# Isolation.net
KiCad netlist of a schematic drawn in Altium Designer
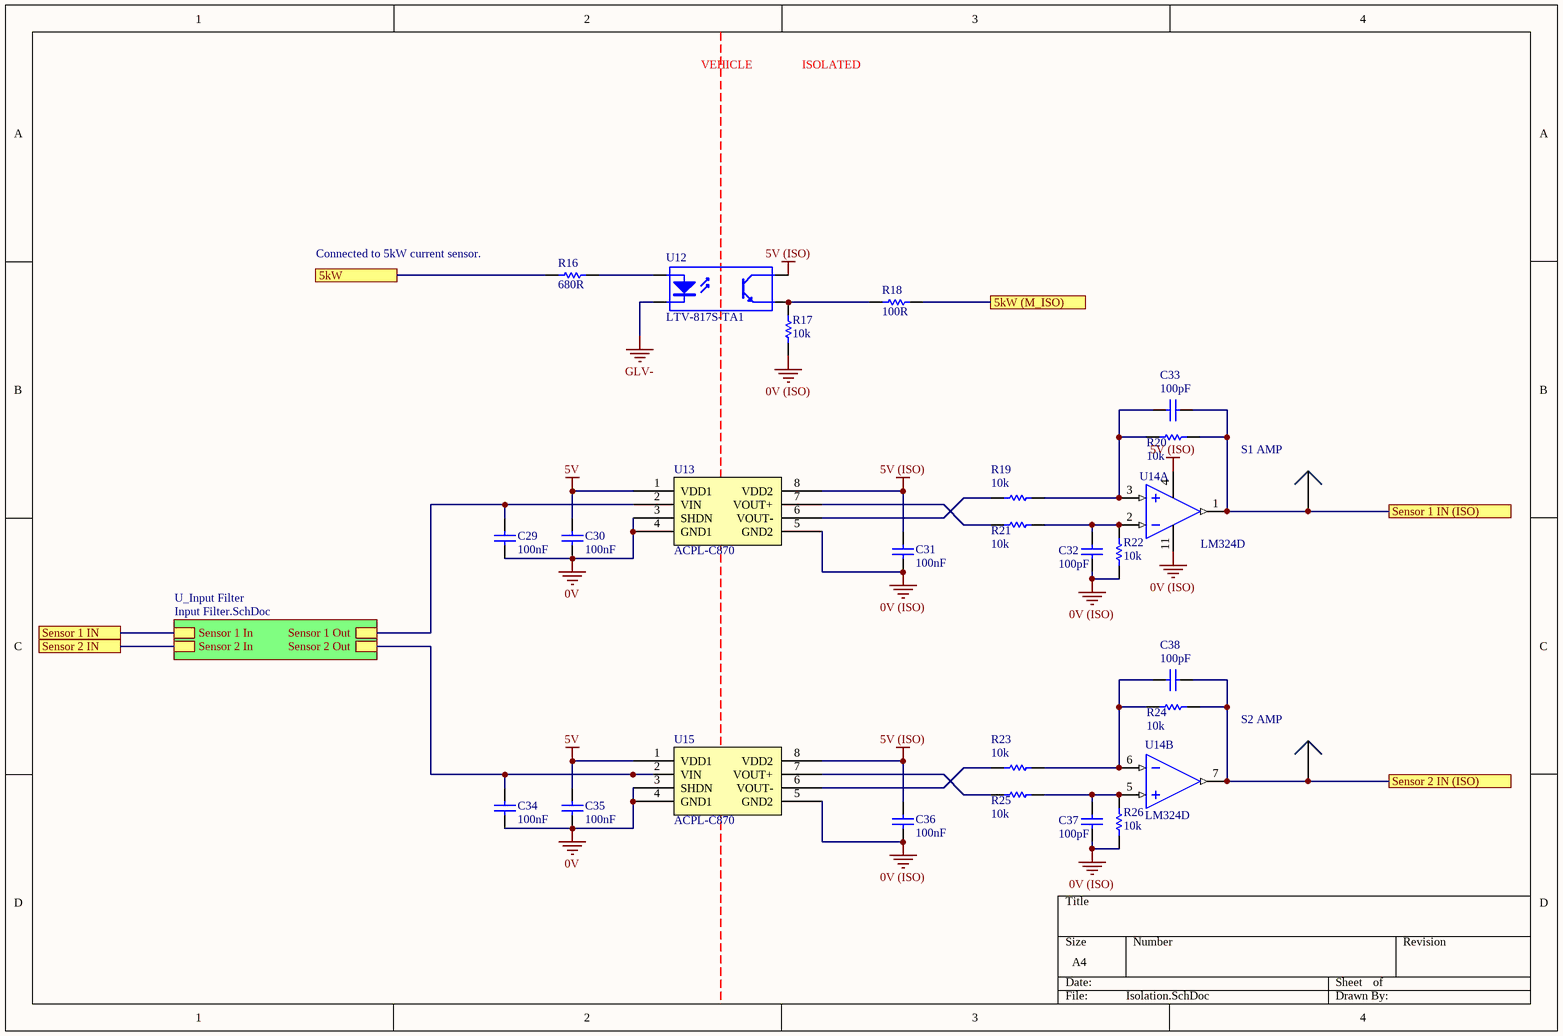
[diagram p0: Isolation.SchDoc]

(export (version "E")
  (design (tool "Eeschema 10.0.6"))
  (components
    (comp (ref "C29")
      (value "100nF")
      (footprint "0805")
      (fields
        (field (name "PART NUMBER") "GCM21BR71H104KA37L")
        (field (name "TOLERANCE") "±10%")
        (field (name "MANUFACTURER") "muRata")
      )
      (libsource (lib "ts_20-standard-library") (part "Capacitor"))
    )
    (comp (ref "C30")
      (value "100nF")
      (footprint "0805")
      (fields
        (field (name "PART NUMBER") "GCM21BR71H104KA37L")
        (field (name "TOLERANCE") "±10%")
        (field (name "MANUFACTURER") "muRata")
      )
      (libsource (lib "ts_20-standard-library") (part "Capacitor"))
    )
    (comp (ref "C31")
      (value "100nF")
      (footprint "0805")
      (fields
        (field (name "PART NUMBER") "GCM21BR71H104KA37L")
        (field (name "TOLERANCE") "±10%")
        (field (name "MANUFACTURER") "muRata")
      )
      (libsource (lib "ts_20-standard-library") (part "Capacitor"))
    )
    (comp (ref "C32")
      (value "100pF")
      (footprint "0805")
      (fields
        (field (name "PART NUMBER") "GCM2165C1H101JA16D")
        (field (name "TOLERANCE") "±5%")
        (field (name "MANUFACTURER") "muRata")
      )
      (libsource (lib "ts_20-standard-library") (part "Capacitor"))
    )
    (comp (ref "C33")
      (value "100pF")
      (footprint "0805")
      (fields
        (field (name "PART NUMBER") "GCM2165C1H101JA16D")
        (field (name "TOLERANCE") "±5%")
        (field (name "MANUFACTURER") "muRata")
      )
      (libsource (lib "ts_20-standard-library") (part "Capacitor"))
    )
    (comp (ref "C34")
      (value "100nF")
      (footprint "0805")
      (fields
        (field (name "PART NUMBER") "GCM21BR71H104KA37L")
        (field (name "TOLERANCE") "±10%")
        (field (name "MANUFACTURER") "muRata")
      )
      (libsource (lib "ts_20-standard-library") (part "Capacitor"))
    )
    (comp (ref "C35")
      (value "100nF")
      (footprint "0805")
      (fields
        (field (name "PART NUMBER") "GCM21BR71H104KA37L")
        (field (name "TOLERANCE") "±10%")
        (field (name "MANUFACTURER") "muRata")
      )
      (libsource (lib "ts_20-standard-library") (part "Capacitor"))
    )
    (comp (ref "C36")
      (value "100nF")
      (footprint "0805")
      (fields
        (field (name "PART NUMBER") "GCM21BR71H104KA37L")
        (field (name "TOLERANCE") "±10%")
        (field (name "MANUFACTURER") "muRata")
      )
      (libsource (lib "ts_20-standard-library") (part "Capacitor"))
    )
    (comp (ref "C37")
      (value "100pF")
      (footprint "0805")
      (fields
        (field (name "PART NUMBER") "GCM2165C1H101JA16D")
        (field (name "TOLERANCE") "±5%")
        (field (name "MANUFACTURER") "muRata")
      )
      (libsource (lib "ts_20-standard-library") (part "Capacitor"))
    )
    (comp (ref "C38")
      (value "100pF")
      (footprint "0805")
      (fields
        (field (name "PART NUMBER") "GCM2165C1H101JA16D")
        (field (name "TOLERANCE") "±5%")
        (field (name "MANUFACTURER") "muRata")
      )
      (libsource (lib "ts_20-standard-library") (part "Capacitor"))
    )
    (comp (ref "R16")
      (value "680R")
      (footprint "0805")
      (fields
        (field (name "PART NUMBER") "RC0805FR07680RL")
        (field (name "MANUFACTURER") "YAGEO")
        (field (name "TOLERANCE") "0.01")
      )
      (libsource (lib "ts_20-standard-library") (part "Resistor"))
    )
    (comp (ref "R17")
      (value "10k")
      (footprint "0805")
      (fields
        (field (name "PART NUMBER") "RC0805FR0710KL")
        (field (name "MANUFACTURER") "YAGEO")
        (field (name "TOLERANCE") "0.01")
      )
      (libsource (lib "ts_20-standard-library") (part "Resistor"))
    )
    (comp (ref "R18")
      (value "100R")
      (footprint "0805")
      (fields
        (field (name "PART NUMBER") "RC0805FR07100RL")
        (field (name "MANUFACTURER") "YAGEO")
        (field (name "TOLERANCE") "0.01")
      )
      (libsource (lib "ts_20-standard-library") (part "Resistor"))
    )
    (comp (ref "R19")
      (value "10k")
      (footprint "0805")
      (fields
        (field (name "PART NUMBER") "RC0805FR0710KL")
        (field (name "MANUFACTURER") "YAGEO")
        (field (name "TOLERANCE") "0.01")
      )
      (libsource (lib "ts_20-standard-library") (part "Resistor"))
    )
    (comp (ref "R20")
      (value "10k")
      (footprint "0805")
      (fields
        (field (name "PART NUMBER") "RC0805FR0710KL")
        (field (name "MANUFACTURER") "YAGEO")
        (field (name "TOLERANCE") "0.01")
      )
      (libsource (lib "ts_20-standard-library") (part "Resistor"))
    )
    (comp (ref "R21")
      (value "10k")
      (footprint "0805")
      (fields
        (field (name "PART NUMBER") "RC0805FR0710KL")
        (field (name "MANUFACTURER") "YAGEO")
        (field (name "TOLERANCE") "0.01")
      )
      (libsource (lib "ts_20-standard-library") (part "Resistor"))
    )
    (comp (ref "R22")
      (value "10k")
      (footprint "0805")
      (fields
        (field (name "PART NUMBER") "RC0805FR0710KL")
        (field (name "MANUFACTURER") "YAGEO")
        (field (name "TOLERANCE") "0.01")
      )
      (libsource (lib "ts_20-standard-library") (part "Resistor"))
    )
    (comp (ref "R23")
      (value "10k")
      (footprint "0805")
      (fields
        (field (name "PART NUMBER") "RC0805FR0710KL")
        (field (name "MANUFACTURER") "YAGEO")
        (field (name "TOLERANCE") "0.01")
      )
      (libsource (lib "ts_20-standard-library") (part "Resistor"))
    )
    (comp (ref "R24")
      (value "10k")
      (footprint "0805")
      (fields
        (field (name "PART NUMBER") "RC0805FR0710KL")
        (field (name "MANUFACTURER") "YAGEO")
        (field (name "TOLERANCE") "0.01")
      )
      (libsource (lib "ts_20-standard-library") (part "Resistor"))
    )
    (comp (ref "R25")
      (value "10k")
      (footprint "0805")
      (fields
        (field (name "PART NUMBER") "RC0805FR0710KL")
        (field (name "MANUFACTURER") "YAGEO")
        (field (name "TOLERANCE") "0.01")
      )
      (libsource (lib "ts_20-standard-library") (part "Resistor"))
    )
    (comp (ref "R26")
      (value "10k")
      (footprint "0805")
      (fields
        (field (name "PART NUMBER") "RC0805FR0710KL")
        (field (name "MANUFACTURER") "YAGEO")
        (field (name "TOLERANCE") "0.01")
      )
      (libsource (lib "ts_20-standard-library") (part "Resistor"))
    )
    (comp (ref "S1 AMP")
      (value "0mm")
      (footprint "SMD Test Point")
      (fields (field (name "PART NUMBER") "SMD Test Point") (field (name "CONTACT") "NA"))
      (libsource (lib "ts_20-standard-connectors") (part "Test Point"))
    )
    (comp (ref "S2 AMP")
      (value "0mm")
      (footprint "SMD Test Point")
      (fields (field (name "PART NUMBER") "SMD Test Point") (field (name "CONTACT") "NA"))
      (libsource (lib "ts_20-standard-connectors") (part "Test Point"))
    )
    (comp (ref "U12")
      (value "LTV-817S-TA1")
      (footprint "ON 4-SMD")
      (description "35V 50ma Optocoupler (VF=1.2V)")
      (fields
        (field (name "MANUFACTURER") "Lite-On Inc")
        (field (name "DIGIKEY PART NUMBER") "160-1893-2-ND")
      )
      (libsource (lib "ts_20-standard-library") (part "LTV-817S-TA1"))
    )
    (comp (ref "U13")
      (value "ACPL-C870")
      (footprint "BROAD 8-SOIC")
      (description "Isolation Amplifier 1 Circuit Differential 8-SO")
      (fields
        (field (name "MANUFACTURER") "Broadcom Limited")
        (field (name "DIGIKEY PART NUMBER") "516-2578-5-ND")
      )
      (libsource (lib "ts_20-standard-library") (part "ACPL-C870"))
    )
    (comp (ref "U14")
      (value "LM324D")
      (footprint "TI 14-SOIC")
      (description "IC OPAMP GP 4 CIRCUIT 14SOIC")
      (fields
        (field (name "MANUFACTURER") "Texas Instruments")
        (field (name "DIGIKEY PART NUMBER") "296-1390-5-ND")
      )
      (libsource (lib "ts_20-standard-library") (part "LM324D"))
    )
    (comp (ref "U15")
      (value "ACPL-C870")
      (footprint "BROAD 8-SOIC")
      (description "Isolation Amplifier 1 Circuit Differential 8-SO")
      (fields
        (field (name "MANUFACTURER") "Broadcom Limited")
        (field (name "DIGIKEY PART NUMBER") "516-2578-5-ND")
      )
      (libsource (lib "ts_20-standard-library") (part "ACPL-C870"))
    )
  )
  (nets
    (net (code "1") (name "/5kW") (class "Default")
      (node (ref "R16") (pin "2") (pinfunction "2_2") (pintype "passive"))
    )
    (net (code "2") (name "/5kW (M_ISO)") (class "Default")
      (node (ref "R18") (pin "1") (pinfunction "1_1") (pintype "passive"))
    )
    (net (code "4") (name "/Sensor 1 IN (ISO)") (class "Default")
      (node (ref "C33") (pin "1") (pinfunction "1_1") (pintype "passive"))
      (node (ref "R20") (pin "2") (pinfunction "2_2") (pintype "passive"))
      (node (ref "S1 AMP") (pin "1") (pinfunction "1_1") (pintype "passive"))
      (node (ref "U14") (pin "1") (pinfunction "1OUT_1") (pintype "output"))
    )
    (net (code "5") (name "/Sensor 1 Out") (class "Default")
      (node (ref "C29") (pin "2") (pinfunction "2_2") (pintype "passive"))
      (node (ref "U13") (pin "2") (pinfunction "VIN_2") (pintype "passive"))
    )
    (net (code "7") (name "/Sensor 2 IN (ISO)") (class "Default")
      (node (ref "C38") (pin "1") (pinfunction "1_1") (pintype "passive"))
      (node (ref "R24") (pin "2") (pinfunction "2_2") (pintype "passive"))
      (node (ref "S2 AMP") (pin "1") (pinfunction "1_1") (pintype "passive"))
      (node (ref "U14") (pin "7") (pinfunction "2OUT_7") (pintype "output"))
    )
    (net (code "8") (name "/Sensor 2 Out") (class "Default")
      (node (ref "C34") (pin "2") (pinfunction "2_2") (pintype "passive"))
      (node (ref "U15") (pin "2") (pinfunction "VIN_2") (pintype "passive"))
    )
    (net (code "9") (name "0V") (class "Default")
      (node (ref "C29") (pin "1") (pinfunction "1_1") (pintype "passive"))
      (node (ref "C30") (pin "1") (pinfunction "1_1") (pintype "passive"))
      (node (ref "C34") (pin "1") (pinfunction "1_1") (pintype "passive"))
      (node (ref "C35") (pin "1") (pinfunction "1_1") (pintype "passive"))
      (node (ref "U13") (pin "3") (pinfunction "SHDN_3") (pintype "passive"))
      (node (ref "U13") (pin "4") (pinfunction "GND1_4") (pintype "passive"))
      (node (ref "U15") (pin "3") (pinfunction "SHDN_3") (pintype "passive"))
      (node (ref "U15") (pin "4") (pinfunction "GND1_4") (pintype "passive"))
    )
    (net (code "10") (name "0V (ISO)") (class "Default")
      (node (ref "C31") (pin "1") (pinfunction "1_1") (pintype "passive"))
      (node (ref "C32") (pin "1") (pinfunction "1_1") (pintype "passive"))
      (node (ref "C36") (pin "1") (pinfunction "1_1") (pintype "passive"))
      (node (ref "C37") (pin "1") (pinfunction "1_1") (pintype "passive"))
      (node (ref "R17") (pin "1") (pinfunction "1_1") (pintype "passive"))
      (node (ref "R22") (pin "1") (pinfunction "1_1") (pintype "passive"))
      (node (ref "R26") (pin "1") (pinfunction "1_1") (pintype "passive"))
      (node (ref "U13") (pin "5") (pinfunction "GND2_5") (pintype "passive"))
      (node (ref "U14") (pin "11") (pinfunction "GND_11") (pintype "power_in"))
      (node (ref "U15") (pin "5") (pinfunction "GND2_5") (pintype "passive"))
    )
    (net (code "11") (name "5V") (class "Default")
      (node (ref "C30") (pin "2") (pinfunction "2_2") (pintype "passive"))
      (node (ref "C35") (pin "2") (pinfunction "2_2") (pintype "passive"))
      (node (ref "U13") (pin "1") (pinfunction "VDD1_1") (pintype "passive"))
      (node (ref "U15") (pin "1") (pinfunction "VDD1_1") (pintype "passive"))
    )
    (net (code "12") (name "5V (ISO)") (class "Default")
      (node (ref "C31") (pin "2") (pinfunction "2_2") (pintype "passive"))
      (node (ref "C36") (pin "2") (pinfunction "2_2") (pintype "passive"))
      (node (ref "U12") (pin "4") (pinfunction "C_4") (pintype "passive"))
      (node (ref "U13") (pin "8") (pinfunction "VDD2_8") (pintype "passive"))
      (node (ref "U14") (pin "4") (pinfunction "VCC_4") (pintype "power_in"))
      (node (ref "U15") (pin "8") (pinfunction "VDD2_8") (pintype "passive"))
    )
    (net (code "13") (name "GLV-") (class "Default")
      (node (ref "U12") (pin "2") (pinfunction "K_2") (pintype "passive"))
    )
    (net (code "14") (name "Net-(C32-Pad2)") (class "Default")
      (node (ref "C32") (pin "2") (pinfunction "2_2") (pintype "passive"))
      (node (ref "R21") (pin "2") (pinfunction "2_2") (pintype "passive"))
      (node (ref "R22") (pin "2") (pinfunction "2_2") (pintype "passive"))
      (node (ref "U14") (pin "2") (pinfunction "1IN+_2") (pintype "input"))
    )
    (net (code "15") (name "Net-(C33-Pad2)") (class "Default")
      (node (ref "C33") (pin "2") (pinfunction "2_2") (pintype "passive"))
      (node (ref "R19") (pin "2") (pinfunction "2_2") (pintype "passive"))
      (node (ref "R20") (pin "1") (pinfunction "1_1") (pintype "passive"))
      (node (ref "U14") (pin "3") (pinfunction "1IN+_3") (pintype "input"))
    )
    (net (code "16") (name "Net-(U12-A)") (class "Default")
      (node (ref "R16") (pin "1") (pinfunction "1_1") (pintype "passive"))
      (node (ref "U12") (pin "1") (pinfunction "A_1") (pintype "passive"))
    )
    (net (code "17") (name "Net-(U12-E)") (class "Default")
      (node (ref "R17") (pin "2") (pinfunction "2_2") (pintype "passive"))
      (node (ref "R18") (pin "2") (pinfunction "2_2") (pintype "passive"))
      (node (ref "U12") (pin "3") (pinfunction "E_3") (pintype "passive"))
    )
    (net (code "18") (name "Net-(U13-VOUT+)") (class "Default")
      (node (ref "R21") (pin "1") (pinfunction "1_1") (pintype "passive"))
      (node (ref "U13") (pin "7") (pinfunction "VOUT+_7") (pintype "passive"))
    )
    (net (code "19") (name "Net-(U13-VOUT-)") (class "Default")
      (node (ref "R19") (pin "1") (pinfunction "1_1") (pintype "passive"))
      (node (ref "U13") (pin "6") (pinfunction "VOUT-_6") (pintype "passive"))
    )
    (net (code "20") (name "Net-(U14B-2IN+)") (class "Default")
      (node (ref "C37") (pin "2") (pinfunction "2_2") (pintype "passive"))
      (node (ref "R25") (pin "2") (pinfunction "2_2") (pintype "passive"))
      (node (ref "R26") (pin "2") (pinfunction "2_2") (pintype "passive"))
      (node (ref "U14") (pin "5") (pinfunction "2IN+_5") (pintype "input"))
    )
    (net (code "21") (name "Net-(U14B-2IN-)") (class "Default")
      (node (ref "C38") (pin "2") (pinfunction "2_2") (pintype "passive"))
      (node (ref "R23") (pin "2") (pinfunction "2_2") (pintype "passive"))
      (node (ref "R24") (pin "1") (pinfunction "1_1") (pintype "passive"))
      (node (ref "U14") (pin "6") (pinfunction "2IN-_6") (pintype "input"))
    )
    (net (code "22") (name "Net-(U15-VOUT+)") (class "Default")
      (node (ref "R25") (pin "1") (pinfunction "1_1") (pintype "passive"))
      (node (ref "U15") (pin "7") (pinfunction "VOUT+_7") (pintype "passive"))
    )
    (net (code "23") (name "Net-(U15-VOUT-)") (class "Default")
      (node (ref "R23") (pin "1") (pinfunction "1_1") (pintype "passive"))
      (node (ref "U15") (pin "6") (pinfunction "VOUT-_6") (pintype "passive"))
    )
  )
)
